# Usb_Hub.net
KiCad netlist of a schematic drawn in EasyEDA Pro
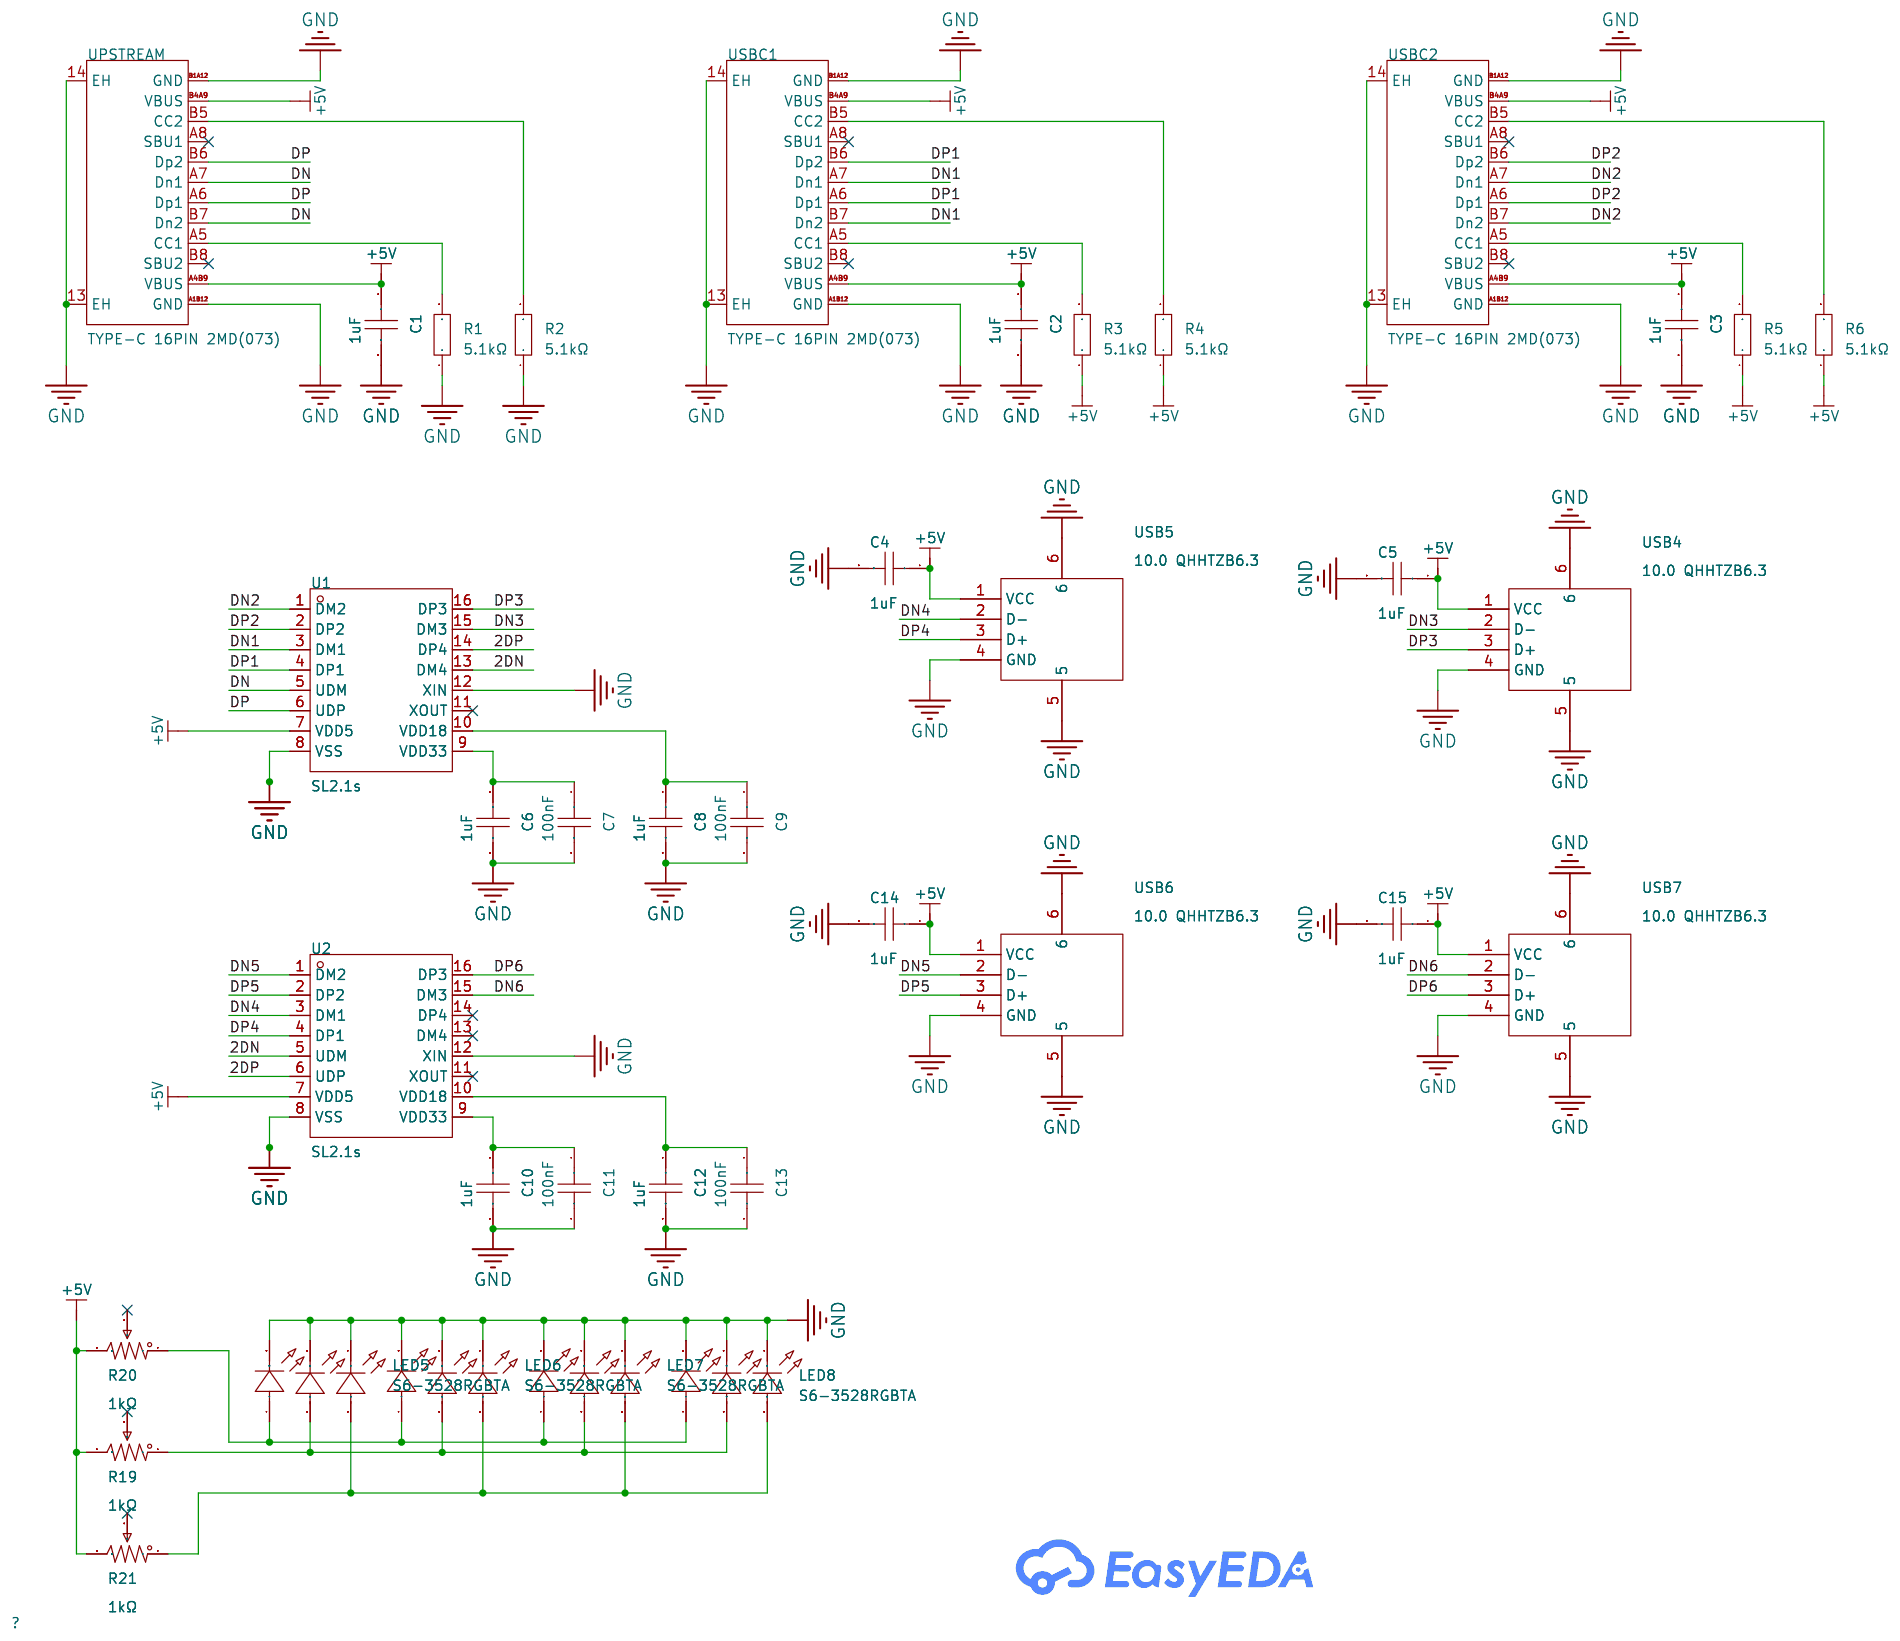
[diagram p0: schematic sheet]

(export (version "E")
  (design (tool "Eeschema 10.0.6"))
  (components
    (comp (ref "C1")
      (value "1uF")
      (footprint "easyedapro:C0603")
      (description "Capacitance:1uF Tolerance:±10% Tolerance:±10% Voltage Rating:50V Temperature Coefficient:X5R")
      (fields
        (field (name "Manufacturer Part") "CL10A105KB8NNNC")
        (field (name "Manufacturer") "SAMSUNG(三星)")
      )
      (libsource (lib "easyedapro") (part "CAP"))
    )
    (comp (ref "C2")
      (value "1uF")
      (footprint "easyedapro:C0603")
      (description "Capacitance:1uF Tolerance:±10% Tolerance:±10% Voltage Rating:50V Temperature Coefficient:X5R")
      (fields
        (field (name "Manufacturer Part") "CL10A105KB8NNNC")
        (field (name "Manufacturer") "SAMSUNG(三星)")
      )
      (libsource (lib "easyedapro") (part "CAP"))
    )
    (comp (ref "C3")
      (value "1uF")
      (footprint "easyedapro:C0603")
      (description "Capacitance:1uF Tolerance:±10% Tolerance:±10% Voltage Rating:50V Temperature Coefficient:X5R")
      (fields
        (field (name "Manufacturer Part") "CL10A105KB8NNNC")
        (field (name "Manufacturer") "SAMSUNG(三星)")
      )
      (libsource (lib "easyedapro") (part "CAP"))
    )
    (comp (ref "C4")
      (value "1uF")
      (footprint "easyedapro:C0603")
      (description "Capacitance:1uF Tolerance:±10% Tolerance:±10% Voltage Rating:50V Temperature Coefficient:X5R")
      (fields
        (field (name "Manufacturer Part") "CL10A105KB8NNNC")
        (field (name "Manufacturer") "SAMSUNG(三星)")
      )
      (libsource (lib "easyedapro") (part "CAP"))
    )
    (comp (ref "C5")
      (value "1uF")
      (footprint "easyedapro:C0603")
      (description "Capacitance:1uF Tolerance:±10% Tolerance:±10% Voltage Rating:50V Temperature Coefficient:X5R")
      (fields
        (field (name "Manufacturer Part") "CL10A105KB8NNNC")
        (field (name "Manufacturer") "SAMSUNG(三星)")
      )
      (libsource (lib "easyedapro") (part "CAP"))
    )
    (comp (ref "C6")
      (value "1uF")
      (footprint "easyedapro:C0603")
      (description "Capacitance:1uF Tolerance:±10% Tolerance:±10% Voltage Rating:50V Temperature Coefficient:X5R")
      (fields
        (field (name "Manufacturer Part") "CL10A105KB8NNNC")
        (field (name "Manufacturer") "SAMSUNG(三星)")
      )
      (libsource (lib "easyedapro") (part "CAP"))
    )
    (comp (ref "C7")
      (value "100nF")
      (footprint "easyedapro:C0603")
      (fields (field (name "Manufacturer Part") "C0603X104K050T") (field (name "Manufacturer") "IHHEC(禾伸堂)"))
      (libsource (lib "easyedapro") (part "CAP"))
    )
    (comp (ref "C8")
      (value "1uF")
      (footprint "easyedapro:C0603")
      (description "Capacitance:1uF Tolerance:±10% Tolerance:±10% Voltage Rating:50V Temperature Coefficient:X5R")
      (fields
        (field (name "Manufacturer Part") "CL10A105KB8NNNC")
        (field (name "Manufacturer") "SAMSUNG(三星)")
      )
      (libsource (lib "easyedapro") (part "CAP"))
    )
    (comp (ref "C9")
      (value "100nF")
      (footprint "easyedapro:C0603")
      (fields (field (name "Manufacturer Part") "C0603X104K050T") (field (name "Manufacturer") "IHHEC(禾伸堂)"))
      (libsource (lib "easyedapro") (part "CAP"))
    )
    (comp (ref "C10")
      (value "1uF")
      (footprint "easyedapro:C0603")
      (description "Capacitance:1uF Tolerance:±10% Tolerance:±10% Voltage Rating:50V Temperature Coefficient:X5R")
      (fields
        (field (name "Manufacturer Part") "CL10A105KB8NNNC")
        (field (name "Manufacturer") "SAMSUNG(三星)")
      )
      (libsource (lib "easyedapro") (part "CAP"))
    )
    (comp (ref "C11")
      (value "100nF")
      (footprint "easyedapro:C0603")
      (fields (field (name "Manufacturer Part") "C0603X104K050T") (field (name "Manufacturer") "IHHEC(禾伸堂)"))
      (libsource (lib "easyedapro") (part "CAP"))
    )
    (comp (ref "C12")
      (value "1uF")
      (footprint "easyedapro:C0603")
      (description "Capacitance:1uF Tolerance:±10% Tolerance:±10% Voltage Rating:50V Temperature Coefficient:X5R")
      (fields
        (field (name "Manufacturer Part") "CL10A105KB8NNNC")
        (field (name "Manufacturer") "SAMSUNG(三星)")
      )
      (libsource (lib "easyedapro") (part "CAP"))
    )
    (comp (ref "C13")
      (value "100nF")
      (footprint "easyedapro:C0603")
      (fields (field (name "Manufacturer Part") "C0603X104K050T") (field (name "Manufacturer") "IHHEC(禾伸堂)"))
      (libsource (lib "easyedapro") (part "CAP"))
    )
    (comp (ref "C14")
      (value "1uF")
      (footprint "easyedapro:C0603")
      (description "Capacitance:1uF Tolerance:±10% Tolerance:±10% Voltage Rating:50V Temperature Coefficient:X5R")
      (fields
        (field (name "Manufacturer Part") "CL10A105KB8NNNC")
        (field (name "Manufacturer") "SAMSUNG(三星)")
      )
      (libsource (lib "easyedapro") (part "CAP"))
    )
    (comp (ref "C15")
      (value "1uF")
      (footprint "easyedapro:C0603")
      (description "Capacitance:1uF Tolerance:±10% Tolerance:±10% Voltage Rating:50V Temperature Coefficient:X5R")
      (fields
        (field (name "Manufacturer Part") "CL10A105KB8NNNC")
        (field (name "Manufacturer") "SAMSUNG(三星)")
      )
      (libsource (lib "easyedapro") (part "CAP"))
    )
    (comp (ref "LED5")
      (value "S6-3528RGBTA")
      (footprint "easyedapro:LED-SMD-6P_S6-3528RGBTA")
      (fields (field (name "Manufacturer") "TUOZHAN(拓展光电)"))
      (libsource (lib "easyedapro") (part "S6-3528RGBTA"))
    )
    (comp (ref "LED6")
      (value "S6-3528RGBTA")
      (footprint "easyedapro:LED-SMD-6P_S6-3528RGBTA")
      (fields (field (name "Manufacturer") "TUOZHAN(拓展光电)"))
      (libsource (lib "easyedapro") (part "S6-3528RGBTA"))
    )
    (comp (ref "LED7")
      (value "S6-3528RGBTA")
      (footprint "easyedapro:LED-SMD-6P_S6-3528RGBTA")
      (fields (field (name "Manufacturer") "TUOZHAN(拓展光电)"))
      (libsource (lib "easyedapro") (part "S6-3528RGBTA"))
    )
    (comp (ref "LED8")
      (value "S6-3528RGBTA")
      (footprint "easyedapro:LED-SMD-6P_S6-3528RGBTA")
      (fields (field (name "Manufacturer") "TUOZHAN(拓展光电)"))
      (libsource (lib "easyedapro") (part "S6-3528RGBTA"))
    )
    (comp (ref "R1")
      (value "5.1kΩ")
      (footprint "easyedapro:R0603")
      (fields
        (field (name "Manufacturer Part") "0603WAF5101T5E")
        (field (name "Manufacturer") "UNI-ROYAL(厚声)")
      )
      (libsource (lib "easyedapro") (part "Res"))
    )
    (comp (ref "R2")
      (value "5.1kΩ")
      (footprint "easyedapro:R0603")
      (fields
        (field (name "Manufacturer Part") "0603WAF5101T5E")
        (field (name "Manufacturer") "UNI-ROYAL(厚声)")
      )
      (libsource (lib "easyedapro") (part "Res"))
    )
    (comp (ref "R3")
      (value "5.1kΩ")
      (footprint "easyedapro:R0603")
      (fields
        (field (name "Manufacturer Part") "0603WAF5101T5E")
        (field (name "Manufacturer") "UNI-ROYAL(厚声)")
      )
      (libsource (lib "easyedapro") (part "Res"))
    )
    (comp (ref "R4")
      (value "5.1kΩ")
      (footprint "easyedapro:R0603")
      (fields
        (field (name "Manufacturer Part") "0603WAF5101T5E")
        (field (name "Manufacturer") "UNI-ROYAL(厚声)")
      )
      (libsource (lib "easyedapro") (part "Res"))
    )
    (comp (ref "R5")
      (value "5.1kΩ")
      (footprint "easyedapro:R0603")
      (fields
        (field (name "Manufacturer Part") "0603WAF5101T5E")
        (field (name "Manufacturer") "UNI-ROYAL(厚声)")
      )
      (libsource (lib "easyedapro") (part "Res"))
    )
    (comp (ref "R6")
      (value "5.1kΩ")
      (footprint "easyedapro:R0603")
      (fields
        (field (name "Manufacturer Part") "0603WAF5101T5E")
        (field (name "Manufacturer") "UNI-ROYAL(厚声)")
      )
      (libsource (lib "easyedapro") (part "Res"))
    )
    (comp (ref "R19")
      (value "1kΩ")
      (footprint "easyedapro:RES-ADJ-SMD_3P-L3.8-W3.6-P1.90-BL")
      (fields (field (name "Manufacturer Part") "TC33X-2-102E") (field (name "Manufacturer") "BOURNS"))
      (libsource (lib "easyedapro") (part "TC33X-2-102E"))
    )
    (comp (ref "R20")
      (value "1kΩ")
      (footprint "easyedapro:RES-ADJ-SMD_3P-L3.8-W3.6-P1.90-BL")
      (fields (field (name "Manufacturer Part") "TC33X-2-102E") (field (name "Manufacturer") "BOURNS"))
      (libsource (lib "easyedapro") (part "TC33X-2-102E"))
    )
    (comp (ref "R21")
      (value "1kΩ")
      (footprint "easyedapro:RES-ADJ-SMD_3P-L3.8-W3.6-P1.90-BL")
      (fields (field (name "Manufacturer Part") "TC33X-2-102E") (field (name "Manufacturer") "BOURNS"))
      (libsource (lib "easyedapro") (part "TC33X-2-102E"))
    )
    (comp (ref "U1")
      (value "SL2.1s")
      (footprint "easyedapro:SSOP-16_L4.6-W2.6-P0.53-LS4.0-BL")
      (fields (field (name "Manufacturer") "CoreChips(和芯润德)"))
      (libsource (lib "easyedapro") (part "SL2.1S"))
    )
    (comp (ref "U2")
      (value "SL2.1s")
      (footprint "easyedapro:SSOP-16_L4.6-W2.6-P0.53-LS4.0-BL")
      (fields (field (name "Manufacturer") "CoreChips(和芯润德)"))
      (libsource (lib "easyedapro") (part "SL2.1S"))
    )
    (comp (ref "UPSTREAM")
      (value "TYPE-C 16PIN 2MD(073)")
      (footprint "easyedapro:USB-C-SMD_TYPE-C-16PIN-2MD-073")
      (fields (field (name "Manufacturer") "SHOU HAN(首韩)"))
      (libsource (lib "easyedapro") (part "TYPE-C 16PIN 2MD(073)"))
    )
    (comp (ref "USB4")
      (value "10.0 QHHTZB6.3")
      (footprint "easyedapro:USB-A-TH_10.0QHHTZB6.3")
      (fields (field (name "Manufacturer") "SHOU HAN(首韩)"))
      (libsource (lib "easyedapro") (part "10.0 QHHTZB6.3"))
    )
    (comp (ref "USB5")
      (value "10.0 QHHTZB6.3")
      (footprint "easyedapro:USB-A-TH_10.0QHHTZB6.3")
      (fields (field (name "Manufacturer") "SHOU HAN(首韩)"))
      (libsource (lib "easyedapro") (part "10.0 QHHTZB6.3"))
    )
    (comp (ref "USB6")
      (value "10.0 QHHTZB6.3")
      (footprint "easyedapro:USB-A-TH_10.0QHHTZB6.3")
      (fields (field (name "Manufacturer") "SHOU HAN(首韩)"))
      (libsource (lib "easyedapro") (part "10.0 QHHTZB6.3"))
    )
    (comp (ref "USB7")
      (value "10.0 QHHTZB6.3")
      (footprint "easyedapro:USB-A-TH_10.0QHHTZB6.3")
      (fields (field (name "Manufacturer") "SHOU HAN(首韩)"))
      (libsource (lib "easyedapro") (part "10.0 QHHTZB6.3"))
    )
    (comp (ref "USBC1")
      (value "TYPE-C 16PIN 2MD(073)")
      (footprint "easyedapro:USB-C-SMD_TYPE-C-16PIN-2MD-073")
      (fields (field (name "Manufacturer") "SHOU HAN(首韩)"))
      (libsource (lib "easyedapro") (part "TYPE-C 16PIN 2MD(073)"))
    )
    (comp (ref "USBC2")
      (value "TYPE-C 16PIN 2MD(073)")
      (footprint "easyedapro:USB-C-SMD_TYPE-C-16PIN-2MD-073")
      (fields (field (name "Manufacturer") "SHOU HAN(首韩)"))
      (libsource (lib "easyedapro") (part "TYPE-C 16PIN 2MD(073)"))
    )
  )
  (nets
    (net (code "1") (name "+5V") (class "Default")
      (node (ref "C1") (pin "1") (pinfunction "1_1") (pintype "input"))
      (node (ref "C14") (pin "1") (pinfunction "1_1") (pintype "input"))
      (node (ref "C15") (pin "1") (pinfunction "1_1") (pintype "input"))
      (node (ref "C2") (pin "1") (pinfunction "1_1") (pintype "input"))
      (node (ref "C3") (pin "1") (pinfunction "1_1") (pintype "input"))
      (node (ref "C4") (pin "1") (pinfunction "1_1") (pintype "input"))
      (node (ref "C5") (pin "1") (pinfunction "1_1") (pintype "input"))
      (node (ref "R19") (pin "3") (pinfunction "3_3") (pintype "unspecified"))
      (node (ref "R20") (pin "3") (pinfunction "3_3") (pintype "unspecified"))
      (node (ref "R21") (pin "3") (pinfunction "3_3") (pintype "unspecified"))
      (node (ref "R3") (pin "1") (pinfunction "1_1") (pintype "input"))
      (node (ref "R4") (pin "1") (pinfunction "1_1") (pintype "input"))
      (node (ref "R5") (pin "1") (pinfunction "1_1") (pintype "input"))
      (node (ref "R6") (pin "1") (pinfunction "1_1") (pintype "input"))
      (node (ref "U1") (pin "7") (pinfunction "VDD5_7") (pintype "unspecified"))
      (node (ref "U2") (pin "7") (pinfunction "VDD5_7") (pintype "unspecified"))
      (node (ref "UPSTREAM") (pin "A4B9") (pinfunction "VBUS_A4B9") (pintype "unspecified"))
      (node (ref "UPSTREAM") (pin "B4A9") (pinfunction "VBUS_B4A9") (pintype "unspecified"))
      (node (ref "USB4") (pin "1") (pinfunction "VCC_1") (pintype "unspecified"))
      (node (ref "USB5") (pin "1") (pinfunction "VCC_1") (pintype "unspecified"))
      (node (ref "USB6") (pin "1") (pinfunction "VCC_1") (pintype "unspecified"))
      (node (ref "USB7") (pin "1") (pinfunction "VCC_1") (pintype "unspecified"))
      (node (ref "USBC1") (pin "A4B9") (pinfunction "VBUS_A4B9") (pintype "unspecified"))
      (node (ref "USBC1") (pin "B4A9") (pinfunction "VBUS_B4A9") (pintype "unspecified"))
      (node (ref "USBC2") (pin "A4B9") (pinfunction "VBUS_A4B9") (pintype "unspecified"))
      (node (ref "USBC2") (pin "B4A9") (pinfunction "VBUS_B4A9") (pintype "unspecified"))
    )
    (net (code "2") (name "/2DN") (class "Default")
      (node (ref "U1") (pin "13") (pinfunction "DM4_13") (pintype "unspecified"))
      (node (ref "U2") (pin "5") (pinfunction "UDM_5") (pintype "unspecified"))
    )
    (net (code "3") (name "/2DP") (class "Default")
      (node (ref "U1") (pin "14") (pinfunction "DP4_14") (pintype "unspecified"))
      (node (ref "U2") (pin "6") (pinfunction "UDP_6") (pintype "unspecified"))
    )
    (net (code "4") (name "/DN") (class "Default")
      (node (ref "U1") (pin "5") (pinfunction "UDM_5") (pintype "unspecified"))
      (node (ref "UPSTREAM") (pin "A7") (pinfunction "Dn1_A7") (pintype "unspecified"))
      (node (ref "UPSTREAM") (pin "B7") (pinfunction "Dn2_B7") (pintype "unspecified"))
    )
    (net (code "5") (name "/DN1") (class "Default")
      (node (ref "U1") (pin "3") (pinfunction "DM1_3") (pintype "unspecified"))
      (node (ref "USBC1") (pin "A7") (pinfunction "Dn1_A7") (pintype "unspecified"))
      (node (ref "USBC1") (pin "B7") (pinfunction "Dn2_B7") (pintype "unspecified"))
    )
    (net (code "6") (name "/DN2") (class "Default")
      (node (ref "U1") (pin "1") (pinfunction "DM2_1") (pintype "unspecified"))
      (node (ref "USBC2") (pin "A7") (pinfunction "Dn1_A7") (pintype "unspecified"))
      (node (ref "USBC2") (pin "B7") (pinfunction "Dn2_B7") (pintype "unspecified"))
    )
    (net (code "7") (name "/DN3") (class "Default")
      (node (ref "U1") (pin "15") (pinfunction "DM3_15") (pintype "unspecified"))
      (node (ref "USB4") (pin "2") (pinfunction "D-_2") (pintype "unspecified"))
    )
    (net (code "8") (name "/DN4") (class "Default")
      (node (ref "U2") (pin "3") (pinfunction "DM1_3") (pintype "unspecified"))
      (node (ref "USB5") (pin "2") (pinfunction "D-_2") (pintype "unspecified"))
    )
    (net (code "9") (name "/DN5") (class "Default")
      (node (ref "U2") (pin "1") (pinfunction "DM2_1") (pintype "unspecified"))
      (node (ref "USB6") (pin "2") (pinfunction "D-_2") (pintype "unspecified"))
    )
    (net (code "10") (name "/DN6") (class "Default")
      (node (ref "U2") (pin "15") (pinfunction "DM3_15") (pintype "unspecified"))
      (node (ref "USB7") (pin "2") (pinfunction "D-_2") (pintype "unspecified"))
    )
    (net (code "11") (name "/DP") (class "Default")
      (node (ref "U1") (pin "6") (pinfunction "UDP_6") (pintype "unspecified"))
      (node (ref "UPSTREAM") (pin "A6") (pinfunction "Dp1_A6") (pintype "unspecified"))
      (node (ref "UPSTREAM") (pin "B6") (pinfunction "Dp2_B6") (pintype "unspecified"))
    )
    (net (code "12") (name "/DP1") (class "Default")
      (node (ref "U1") (pin "4") (pinfunction "DP1_4") (pintype "unspecified"))
      (node (ref "USBC1") (pin "A6") (pinfunction "Dp1_A6") (pintype "unspecified"))
      (node (ref "USBC1") (pin "B6") (pinfunction "Dp2_B6") (pintype "unspecified"))
    )
    (net (code "13") (name "/DP2") (class "Default")
      (node (ref "U1") (pin "2") (pinfunction "DP2_2") (pintype "unspecified"))
      (node (ref "USBC2") (pin "A6") (pinfunction "Dp1_A6") (pintype "unspecified"))
      (node (ref "USBC2") (pin "B6") (pinfunction "Dp2_B6") (pintype "unspecified"))
    )
    (net (code "14") (name "/DP3") (class "Default")
      (node (ref "U1") (pin "16") (pinfunction "DP3_16") (pintype "unspecified"))
      (node (ref "USB4") (pin "3") (pinfunction "D+_3") (pintype "unspecified"))
    )
    (net (code "15") (name "/DP4") (class "Default")
      (node (ref "U2") (pin "4") (pinfunction "DP1_4") (pintype "unspecified"))
      (node (ref "USB5") (pin "3") (pinfunction "D+_3") (pintype "unspecified"))
    )
    (net (code "16") (name "/DP5") (class "Default")
      (node (ref "U2") (pin "2") (pinfunction "DP2_2") (pintype "unspecified"))
      (node (ref "USB6") (pin "3") (pinfunction "D+_3") (pintype "unspecified"))
    )
    (net (code "17") (name "/DP6") (class "Default")
      (node (ref "U2") (pin "16") (pinfunction "DP3_16") (pintype "unspecified"))
      (node (ref "USB7") (pin "3") (pinfunction "D+_3") (pintype "unspecified"))
    )
    (net (code "18") (name "GND") (class "Default")
      (node (ref "C1") (pin "2") (pinfunction "2_2") (pintype "input"))
      (node (ref "C10") (pin "2") (pinfunction "2_2") (pintype "input"))
      (node (ref "C11") (pin "2") (pinfunction "2_2") (pintype "input"))
      (node (ref "C12") (pin "2") (pinfunction "2_2") (pintype "input"))
      (node (ref "C13") (pin "2") (pinfunction "2_2") (pintype "input"))
      (node (ref "C14") (pin "2") (pinfunction "2_2") (pintype "input"))
      (node (ref "C15") (pin "2") (pinfunction "2_2") (pintype "input"))
      (node (ref "C2") (pin "2") (pinfunction "2_2") (pintype "input"))
      (node (ref "C3") (pin "2") (pinfunction "2_2") (pintype "input"))
      (node (ref "C4") (pin "2") (pinfunction "2_2") (pintype "input"))
      (node (ref "C5") (pin "2") (pinfunction "2_2") (pintype "input"))
      (node (ref "C6") (pin "2") (pinfunction "2_2") (pintype "input"))
      (node (ref "C7") (pin "2") (pinfunction "2_2") (pintype "input"))
      (node (ref "C8") (pin "2") (pinfunction "2_2") (pintype "input"))
      (node (ref "C9") (pin "2") (pinfunction "2_2") (pintype "input"))
      (node (ref "LED5") (pin "1") (pinfunction "1_1") (pintype "unspecified"))
      (node (ref "LED5") (pin "2") (pinfunction "2_2") (pintype "unspecified"))
      (node (ref "LED5") (pin "3") (pinfunction "3_3") (pintype "unspecified"))
      (node (ref "LED6") (pin "1") (pinfunction "1_1") (pintype "unspecified"))
      (node (ref "LED6") (pin "2") (pinfunction "2_2") (pintype "unspecified"))
      (node (ref "LED6") (pin "3") (pinfunction "3_3") (pintype "unspecified"))
      (node (ref "LED7") (pin "1") (pinfunction "1_1") (pintype "unspecified"))
      (node (ref "LED7") (pin "2") (pinfunction "2_2") (pintype "unspecified"))
      (node (ref "LED7") (pin "3") (pinfunction "3_3") (pintype "unspecified"))
      (node (ref "LED8") (pin "1") (pinfunction "1_1") (pintype "unspecified"))
      (node (ref "LED8") (pin "2") (pinfunction "2_2") (pintype "unspecified"))
      (node (ref "LED8") (pin "3") (pinfunction "3_3") (pintype "unspecified"))
      (node (ref "R1") (pin "1") (pinfunction "1_1") (pintype "input"))
      (node (ref "R2") (pin "1") (pinfunction "1_1") (pintype "input"))
      (node (ref "U1") (pin "12") (pinfunction "XIN_12") (pintype "unspecified"))
      (node (ref "U1") (pin "8") (pinfunction "VSS_8") (pintype "unspecified"))
      (node (ref "U2") (pin "12") (pinfunction "XIN_12") (pintype "unspecified"))
      (node (ref "U2") (pin "8") (pinfunction "VSS_8") (pintype "unspecified"))
      (node (ref "UPSTREAM") (pin "13") (pinfunction "EH_13") (pintype "unspecified"))
      (node (ref "UPSTREAM") (pin "14") (pinfunction "EH_14") (pintype "unspecified"))
      (node (ref "UPSTREAM") (pin "A1B12") (pinfunction "GND_A1B12") (pintype "unspecified"))
      (node (ref "UPSTREAM") (pin "B1A12") (pinfunction "GND_B1A12") (pintype "unspecified"))
      (node (ref "USB4") (pin "4") (pinfunction "GND_4") (pintype "unspecified"))
      (node (ref "USB4") (pin "5") (pinfunction "5_5") (pintype "unspecified"))
      (node (ref "USB4") (pin "6") (pinfunction "6_6") (pintype "unspecified"))
      (node (ref "USB5") (pin "4") (pinfunction "GND_4") (pintype "unspecified"))
      (node (ref "USB5") (pin "5") (pinfunction "5_5") (pintype "unspecified"))
      (node (ref "USB5") (pin "6") (pinfunction "6_6") (pintype "unspecified"))
      (node (ref "USB6") (pin "4") (pinfunction "GND_4") (pintype "unspecified"))
      (node (ref "USB6") (pin "5") (pinfunction "5_5") (pintype "unspecified"))
      (node (ref "USB6") (pin "6") (pinfunction "6_6") (pintype "unspecified"))
      (node (ref "USB7") (pin "4") (pinfunction "GND_4") (pintype "unspecified"))
      (node (ref "USB7") (pin "5") (pinfunction "5_5") (pintype "unspecified"))
      (node (ref "USB7") (pin "6") (pinfunction "6_6") (pintype "unspecified"))
      (node (ref "USBC1") (pin "13") (pinfunction "EH_13") (pintype "unspecified"))
      (node (ref "USBC1") (pin "14") (pinfunction "EH_14") (pintype "unspecified"))
      (node (ref "USBC1") (pin "A1B12") (pinfunction "GND_A1B12") (pintype "unspecified"))
      (node (ref "USBC1") (pin "B1A12") (pinfunction "GND_B1A12") (pintype "unspecified"))
      (node (ref "USBC2") (pin "13") (pinfunction "EH_13") (pintype "unspecified"))
      (node (ref "USBC2") (pin "14") (pinfunction "EH_14") (pintype "unspecified"))
      (node (ref "USBC2") (pin "A1B12") (pinfunction "GND_A1B12") (pintype "unspecified"))
      (node (ref "USBC2") (pin "B1A12") (pinfunction "GND_B1A12") (pintype "unspecified"))
    )
    (net (code "19") (name "Net-(LED5-Pad4)") (class "Default")
      (node (ref "LED5") (pin "4") (pinfunction "4_4") (pintype "unspecified"))
      (node (ref "LED6") (pin "4") (pinfunction "4_4") (pintype "unspecified"))
      (node (ref "LED7") (pin "4") (pinfunction "4_4") (pintype "unspecified"))
      (node (ref "LED8") (pin "4") (pinfunction "4_4") (pintype "unspecified"))
      (node (ref "R20") (pin "1") (pinfunction "1_1") (pintype "unspecified"))
    )
    (net (code "20") (name "Net-(LED5-Pad5)") (class "Default")
      (node (ref "LED5") (pin "5") (pinfunction "5_5") (pintype "unspecified"))
      (node (ref "LED6") (pin "5") (pinfunction "5_5") (pintype "unspecified"))
      (node (ref "LED7") (pin "5") (pinfunction "5_5") (pintype "unspecified"))
      (node (ref "LED8") (pin "5") (pinfunction "5_5") (pintype "unspecified"))
      (node (ref "R19") (pin "1") (pinfunction "1_1") (pintype "unspecified"))
    )
    (net (code "21") (name "Net-(LED5-Pad6)") (class "Default")
      (node (ref "LED5") (pin "6") (pinfunction "6_6") (pintype "unspecified"))
      (node (ref "LED6") (pin "6") (pinfunction "6_6") (pintype "unspecified"))
      (node (ref "LED7") (pin "6") (pinfunction "6_6") (pintype "unspecified"))
      (node (ref "LED8") (pin "6") (pinfunction "6_6") (pintype "unspecified"))
      (node (ref "R21") (pin "1") (pinfunction "1_1") (pintype "unspecified"))
    )
    (net (code "22") (name "Net-(U1-VDD18)") (class "Default")
      (node (ref "C8") (pin "1") (pinfunction "1_1") (pintype "input"))
      (node (ref "C9") (pin "1") (pinfunction "1_1") (pintype "input"))
      (node (ref "U1") (pin "10") (pinfunction "VDD18_10") (pintype "unspecified"))
    )
    (net (code "23") (name "Net-(U1-VDD33)") (class "Default")
      (node (ref "C6") (pin "1") (pinfunction "1_1") (pintype "input"))
      (node (ref "C7") (pin "1") (pinfunction "1_1") (pintype "input"))
      (node (ref "U1") (pin "9") (pinfunction "VDD33_9") (pintype "unspecified"))
    )
    (net (code "24") (name "Net-(U2-VDD18)") (class "Default")
      (node (ref "C12") (pin "1") (pinfunction "1_1") (pintype "input"))
      (node (ref "C13") (pin "1") (pinfunction "1_1") (pintype "input"))
      (node (ref "U2") (pin "10") (pinfunction "VDD18_10") (pintype "unspecified"))
    )
    (net (code "25") (name "Net-(U2-VDD33)") (class "Default")
      (node (ref "C10") (pin "1") (pinfunction "1_1") (pintype "input"))
      (node (ref "C11") (pin "1") (pinfunction "1_1") (pintype "input"))
      (node (ref "U2") (pin "9") (pinfunction "VDD33_9") (pintype "unspecified"))
    )
    (net (code "26") (name "Net-(UPSTREAM-CC1)") (class "Default")
      (node (ref "R1") (pin "2") (pinfunction "2_2") (pintype "input"))
      (node (ref "UPSTREAM") (pin "A5") (pinfunction "CC1_A5") (pintype "unspecified"))
    )
    (net (code "27") (name "Net-(UPSTREAM-CC2)") (class "Default")
      (node (ref "R2") (pin "2") (pinfunction "2_2") (pintype "input"))
      (node (ref "UPSTREAM") (pin "B5") (pinfunction "CC2_B5") (pintype "unspecified"))
    )
    (net (code "28") (name "Net-(USBC1-CC1)") (class "Default")
      (node (ref "R3") (pin "2") (pinfunction "2_2") (pintype "input"))
      (node (ref "USBC1") (pin "A5") (pinfunction "CC1_A5") (pintype "unspecified"))
    )
    (net (code "29") (name "Net-(USBC1-CC2)") (class "Default")
      (node (ref "R4") (pin "2") (pinfunction "2_2") (pintype "input"))
      (node (ref "USBC1") (pin "B5") (pinfunction "CC2_B5") (pintype "unspecified"))
    )
    (net (code "30") (name "Net-(USBC2-CC1)") (class "Default")
      (node (ref "R5") (pin "2") (pinfunction "2_2") (pintype "input"))
      (node (ref "USBC2") (pin "A5") (pinfunction "CC1_A5") (pintype "unspecified"))
    )
    (net (code "31") (name "Net-(USBC2-CC2)") (class "Default")
      (node (ref "R6") (pin "2") (pinfunction "2_2") (pintype "input"))
      (node (ref "USBC2") (pin "B5") (pinfunction "CC2_B5") (pintype "unspecified"))
    )
    (net (code "32") (name "unconnected-(R19-Pad2)") (class "Default")
      (node (ref "R19") (pin "2") (pinfunction "2_2") (pintype "unspecified+no_connect"))
    )
    (net (code "33") (name "unconnected-(R20-Pad2)") (class "Default")
      (node (ref "R20") (pin "2") (pinfunction "2_2") (pintype "unspecified+no_connect"))
    )
    (net (code "34") (name "unconnected-(R21-Pad2)") (class "Default")
      (node (ref "R21") (pin "2") (pinfunction "2_2") (pintype "unspecified+no_connect"))
    )
    (net (code "35") (name "unconnected-(U1-XOUT-Pad11)") (class "Default")
      (node (ref "U1") (pin "11") (pinfunction "XOUT_11") (pintype "unspecified+no_connect"))
    )
    (net (code "36") (name "unconnected-(U2-DM4-Pad13)") (class "Default")
      (node (ref "U2") (pin "13") (pinfunction "DM4_13") (pintype "unspecified+no_connect"))
    )
    (net (code "37") (name "unconnected-(U2-DP4-Pad14)") (class "Default")
      (node (ref "U2") (pin "14") (pinfunction "DP4_14") (pintype "unspecified+no_connect"))
    )
    (net (code "38") (name "unconnected-(U2-XOUT-Pad11)") (class "Default")
      (node (ref "U2") (pin "11") (pinfunction "XOUT_11") (pintype "unspecified+no_connect"))
    )
    (net (code "39") (name "unconnected-(UPSTREAM-SBU1-PadA8)") (class "Default")
      (node (ref "UPSTREAM") (pin "A8") (pinfunction "SBU1_A8") (pintype "unspecified+no_connect"))
    )
    (net (code "40") (name "unconnected-(UPSTREAM-SBU2-PadB8)") (class "Default")
      (node (ref "UPSTREAM") (pin "B8") (pinfunction "SBU2_B8") (pintype "unspecified+no_connect"))
    )
    (net (code "41") (name "unconnected-(USBC1-SBU1-PadA8)") (class "Default")
      (node (ref "USBC1") (pin "A8") (pinfunction "SBU1_A8") (pintype "unspecified+no_connect"))
    )
    (net (code "42") (name "unconnected-(USBC1-SBU2-PadB8)") (class "Default")
      (node (ref "USBC1") (pin "B8") (pinfunction "SBU2_B8") (pintype "unspecified+no_connect"))
    )
    (net (code "43") (name "unconnected-(USBC2-SBU1-PadA8)") (class "Default")
      (node (ref "USBC2") (pin "A8") (pinfunction "SBU1_A8") (pintype "unspecified+no_connect"))
    )
    (net (code "44") (name "unconnected-(USBC2-SBU2-PadB8)") (class "Default")
      (node (ref "USBC2") (pin "B8") (pinfunction "SBU2_B8") (pintype "unspecified+no_connect"))
    )
  )
)
